# Pendu_LED_Arrow.net
KiCad netlist of a schematic drawn in EasyEDA
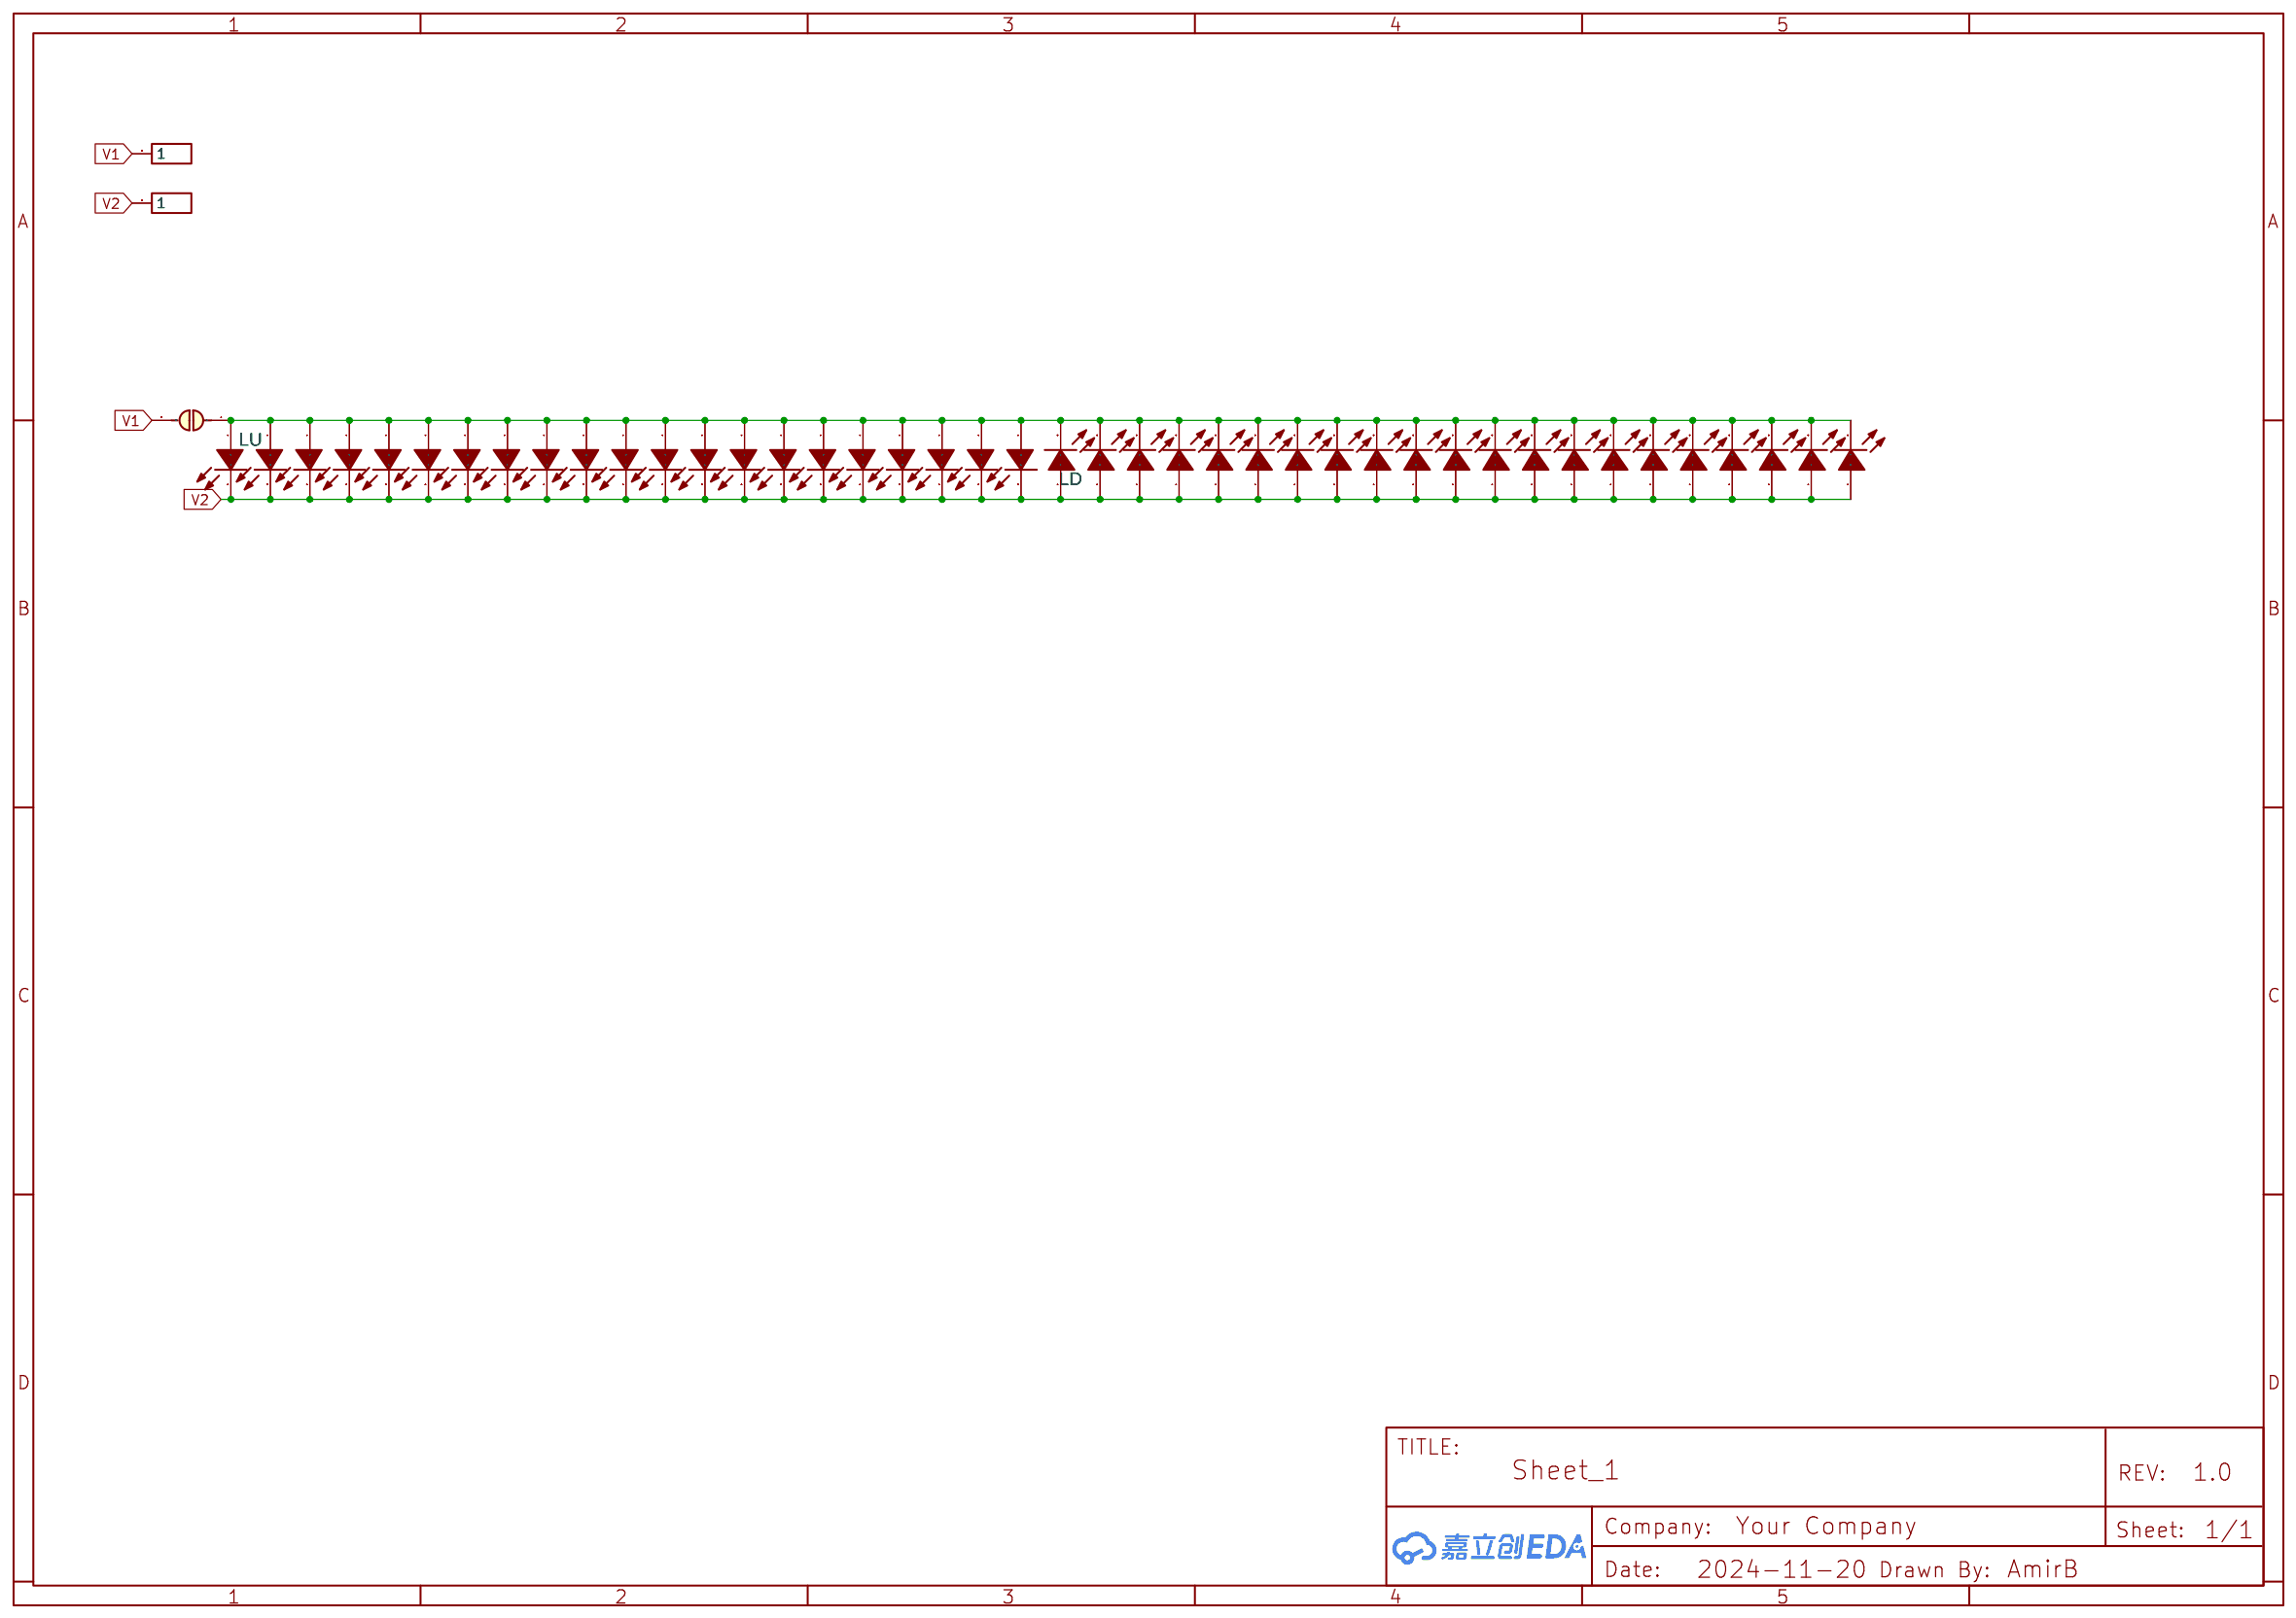
[diagram p0: schematic sheet]

(export (version "E")
  (design (tool "Eeschema 10.0.6"))
  (components
    (comp (ref "J1")
      (value "HDR-M-2.54_1x1")
      (fields (field (name "BOM_Supplier Part") "C81276"))
      (libsource (lib "") (part "HDR-M-2.54_1x1"))
    )
    (comp (ref "J2")
      (value "HDR-M-2.54_1x1")
      (fields (field (name "BOM_Supplier Part") "C81276"))
      (libsource (lib "") (part "HDR-M-2.54_1x1"))
    )
    (comp (ref "JU1") (value "JUMPER-RESET") (libsource (lib "") (part "JUMPER-SMT_2")))
    (comp (ref "LD")
      (value "FC-2012HRK-620D")
      (fields (field (name "Manufacturer Part") "NCD0805R1") (field (name "Manufacturer") "国星光电"))
      (libsource (lib "") (part "FC-2012HRK-620D_1"))
    )
    (comp (ref "LD1")
      (value "FC-2012HRK-620D")
      (fields (field (name "Manufacturer Part") "NCD0805R1") (field (name "Manufacturer") "国星光电"))
      (libsource (lib "") (part "FC-2012HRK-620D_1"))
    )
    (comp (ref "LD2")
      (value "FC-2012HRK-620D")
      (fields (field (name "Manufacturer Part") "NCD0805R1") (field (name "Manufacturer") "国星光电"))
      (libsource (lib "") (part "FC-2012HRK-620D_1"))
    )
    (comp (ref "LD3")
      (value "FC-2012HRK-620D")
      (fields (field (name "Manufacturer Part") "NCD0805R1") (field (name "Manufacturer") "国星光电"))
      (libsource (lib "") (part "FC-2012HRK-620D_1"))
    )
    (comp (ref "LD4")
      (value "FC-2012HRK-620D")
      (fields (field (name "Manufacturer Part") "NCD0805R1") (field (name "Manufacturer") "国星光电"))
      (libsource (lib "") (part "FC-2012HRK-620D_1"))
    )
    (comp (ref "LD5")
      (value "FC-2012HRK-620D")
      (fields (field (name "Manufacturer Part") "NCD0805R1") (field (name "Manufacturer") "国星光电"))
      (libsource (lib "") (part "FC-2012HRK-620D_1"))
    )
    (comp (ref "LD6")
      (value "FC-2012HRK-620D")
      (fields (field (name "Manufacturer Part") "NCD0805R1") (field (name "Manufacturer") "国星光电"))
      (libsource (lib "") (part "FC-2012HRK-620D_1"))
    )
    (comp (ref "LD7")
      (value "FC-2012HRK-620D")
      (fields (field (name "Manufacturer Part") "NCD0805R1") (field (name "Manufacturer") "国星光电"))
      (libsource (lib "") (part "FC-2012HRK-620D_1"))
    )
    (comp (ref "LD8")
      (value "FC-2012HRK-620D")
      (fields (field (name "Manufacturer Part") "NCD0805R1") (field (name "Manufacturer") "国星光电"))
      (libsource (lib "") (part "FC-2012HRK-620D_1"))
    )
    (comp (ref "LD9")
      (value "FC-2012HRK-620D")
      (fields (field (name "Manufacturer Part") "NCD0805R1") (field (name "Manufacturer") "国星光电"))
      (libsource (lib "") (part "FC-2012HRK-620D_1"))
    )
    (comp (ref "LD10")
      (value "FC-2012HRK-620D")
      (fields (field (name "Manufacturer Part") "NCD0805R1") (field (name "Manufacturer") "国星光电"))
      (libsource (lib "") (part "FC-2012HRK-620D_1"))
    )
    (comp (ref "LD11")
      (value "FC-2012HRK-620D")
      (fields (field (name "Manufacturer Part") "NCD0805R1") (field (name "Manufacturer") "国星光电"))
      (libsource (lib "") (part "FC-2012HRK-620D_1"))
    )
    (comp (ref "LD12")
      (value "FC-2012HRK-620D")
      (fields (field (name "Manufacturer Part") "NCD0805R1") (field (name "Manufacturer") "国星光电"))
      (libsource (lib "") (part "FC-2012HRK-620D_1"))
    )
    (comp (ref "LD13")
      (value "FC-2012HRK-620D")
      (fields (field (name "Manufacturer Part") "NCD0805R1") (field (name "Manufacturer") "国星光电"))
      (libsource (lib "") (part "FC-2012HRK-620D_1"))
    )
    (comp (ref "LD14")
      (value "FC-2012HRK-620D")
      (fields (field (name "Manufacturer Part") "NCD0805R1") (field (name "Manufacturer") "国星光电"))
      (libsource (lib "") (part "FC-2012HRK-620D_1"))
    )
    (comp (ref "LD15")
      (value "FC-2012HRK-620D")
      (fields (field (name "Manufacturer Part") "NCD0805R1") (field (name "Manufacturer") "国星光电"))
      (libsource (lib "") (part "FC-2012HRK-620D_1"))
    )
    (comp (ref "LD16")
      (value "FC-2012HRK-620D")
      (fields (field (name "Manufacturer Part") "NCD0805R1") (field (name "Manufacturer") "国星光电"))
      (libsource (lib "") (part "FC-2012HRK-620D_1"))
    )
    (comp (ref "LD17")
      (value "FC-2012HRK-620D")
      (fields (field (name "Manufacturer Part") "NCD0805R1") (field (name "Manufacturer") "国星光电"))
      (libsource (lib "") (part "FC-2012HRK-620D_1"))
    )
    (comp (ref "LD18")
      (value "FC-2012HRK-620D")
      (fields (field (name "Manufacturer Part") "NCD0805R1") (field (name "Manufacturer") "国星光电"))
      (libsource (lib "") (part "FC-2012HRK-620D_1"))
    )
    (comp (ref "LD19")
      (value "FC-2012HRK-620D")
      (fields (field (name "Manufacturer Part") "NCD0805R1") (field (name "Manufacturer") "国星光电"))
      (libsource (lib "") (part "FC-2012HRK-620D_1"))
    )
    (comp (ref "LD20")
      (value "FC-2012HRK-620D")
      (fields (field (name "Manufacturer Part") "NCD0805R1") (field (name "Manufacturer") "国星光电"))
      (libsource (lib "") (part "FC-2012HRK-620D_1"))
    )
    (comp (ref "LU")
      (value "FC-2012HRK-620D")
      (fields (field (name "Manufacturer Part") "NCD0805R1") (field (name "Manufacturer") "国星光电"))
      (libsource (lib "") (part "FC-2012HRK-620D"))
    )
    (comp (ref "LU1")
      (value "FC-2012HRK-620D")
      (fields (field (name "Manufacturer Part") "NCD0805R1") (field (name "Manufacturer") "国星光电"))
      (libsource (lib "") (part "FC-2012HRK-620D"))
    )
    (comp (ref "LU2")
      (value "FC-2012HRK-620D")
      (fields (field (name "Manufacturer Part") "NCD0805R1") (field (name "Manufacturer") "国星光电"))
      (libsource (lib "") (part "FC-2012HRK-620D"))
    )
    (comp (ref "LU3")
      (value "FC-2012HRK-620D")
      (fields (field (name "Manufacturer Part") "NCD0805R1") (field (name "Manufacturer") "国星光电"))
      (libsource (lib "") (part "FC-2012HRK-620D"))
    )
    (comp (ref "LU4")
      (value "FC-2012HRK-620D")
      (fields (field (name "Manufacturer Part") "NCD0805R1") (field (name "Manufacturer") "国星光电"))
      (libsource (lib "") (part "FC-2012HRK-620D"))
    )
    (comp (ref "LU5")
      (value "FC-2012HRK-620D")
      (fields (field (name "Manufacturer Part") "NCD0805R1") (field (name "Manufacturer") "国星光电"))
      (libsource (lib "") (part "FC-2012HRK-620D"))
    )
    (comp (ref "LU6")
      (value "FC-2012HRK-620D")
      (fields (field (name "Manufacturer Part") "NCD0805R1") (field (name "Manufacturer") "国星光电"))
      (libsource (lib "") (part "FC-2012HRK-620D"))
    )
    (comp (ref "LU7")
      (value "FC-2012HRK-620D")
      (fields (field (name "Manufacturer Part") "NCD0805R1") (field (name "Manufacturer") "国星光电"))
      (libsource (lib "") (part "FC-2012HRK-620D"))
    )
    (comp (ref "LU8")
      (value "FC-2012HRK-620D")
      (fields (field (name "Manufacturer Part") "NCD0805R1") (field (name "Manufacturer") "国星光电"))
      (libsource (lib "") (part "FC-2012HRK-620D"))
    )
    (comp (ref "LU9")
      (value "FC-2012HRK-620D")
      (fields (field (name "Manufacturer Part") "NCD0805R1") (field (name "Manufacturer") "国星光电"))
      (libsource (lib "") (part "FC-2012HRK-620D"))
    )
    (comp (ref "LU10")
      (value "FC-2012HRK-620D")
      (fields (field (name "Manufacturer Part") "NCD0805R1") (field (name "Manufacturer") "国星光电"))
      (libsource (lib "") (part "FC-2012HRK-620D"))
    )
    (comp (ref "LU11")
      (value "FC-2012HRK-620D")
      (fields (field (name "Manufacturer Part") "NCD0805R1") (field (name "Manufacturer") "国星光电"))
      (libsource (lib "") (part "FC-2012HRK-620D"))
    )
    (comp (ref "LU12")
      (value "FC-2012HRK-620D")
      (fields (field (name "Manufacturer Part") "NCD0805R1") (field (name "Manufacturer") "国星光电"))
      (libsource (lib "") (part "FC-2012HRK-620D"))
    )
    (comp (ref "LU13")
      (value "FC-2012HRK-620D")
      (fields (field (name "Manufacturer Part") "NCD0805R1") (field (name "Manufacturer") "国星光电"))
      (libsource (lib "") (part "FC-2012HRK-620D"))
    )
    (comp (ref "LU14")
      (value "FC-2012HRK-620D")
      (fields (field (name "Manufacturer Part") "NCD0805R1") (field (name "Manufacturer") "国星光电"))
      (libsource (lib "") (part "FC-2012HRK-620D"))
    )
    (comp (ref "LU15")
      (value "FC-2012HRK-620D")
      (fields (field (name "Manufacturer Part") "NCD0805R1") (field (name "Manufacturer") "国星光电"))
      (libsource (lib "") (part "FC-2012HRK-620D"))
    )
    (comp (ref "LU16")
      (value "FC-2012HRK-620D")
      (fields (field (name "Manufacturer Part") "NCD0805R1") (field (name "Manufacturer") "国星光电"))
      (libsource (lib "") (part "FC-2012HRK-620D"))
    )
    (comp (ref "LU17")
      (value "FC-2012HRK-620D")
      (fields (field (name "Manufacturer Part") "NCD0805R1") (field (name "Manufacturer") "国星光电"))
      (libsource (lib "") (part "FC-2012HRK-620D"))
    )
    (comp (ref "LU18")
      (value "FC-2012HRK-620D")
      (fields (field (name "Manufacturer Part") "NCD0805R1") (field (name "Manufacturer") "国星光电"))
      (libsource (lib "") (part "FC-2012HRK-620D"))
    )
    (comp (ref "LU19")
      (value "FC-2012HRK-620D")
      (fields (field (name "Manufacturer Part") "NCD0805R1") (field (name "Manufacturer") "国星光电"))
      (libsource (lib "") (part "FC-2012HRK-620D"))
    )
    (comp (ref "LU20")
      (value "FC-2012HRK-620D")
      (fields (field (name "Manufacturer Part") "NCD0805R1") (field (name "Manufacturer") "国星光电"))
      (libsource (lib "") (part "FC-2012HRK-620D"))
    )
  )
  (nets
    (net (code "1") (name "Net-(LD--)") (class "Default")
      (node (ref "JU1") (pin "1") (pinfunction "1_1") (pintype "bidirectional"))
      (node (ref "LD") (pin "2") (pinfunction "-_2") (pintype "unspecified"))
      (node (ref "LD1") (pin "2") (pinfunction "-_2") (pintype "unspecified"))
      (node (ref "LD10") (pin "2") (pinfunction "-_2") (pintype "unspecified"))
      (node (ref "LD11") (pin "2") (pinfunction "-_2") (pintype "unspecified"))
      (node (ref "LD12") (pin "2") (pinfunction "-_2") (pintype "unspecified"))
      (node (ref "LD13") (pin "2") (pinfunction "-_2") (pintype "unspecified"))
      (node (ref "LD14") (pin "2") (pinfunction "-_2") (pintype "unspecified"))
      (node (ref "LD15") (pin "2") (pinfunction "-_2") (pintype "unspecified"))
      (node (ref "LD16") (pin "2") (pinfunction "-_2") (pintype "unspecified"))
      (node (ref "LD17") (pin "2") (pinfunction "-_2") (pintype "unspecified"))
      (node (ref "LD18") (pin "2") (pinfunction "-_2") (pintype "unspecified"))
      (node (ref "LD19") (pin "2") (pinfunction "-_2") (pintype "unspecified"))
      (node (ref "LD2") (pin "2") (pinfunction "-_2") (pintype "unspecified"))
      (node (ref "LD20") (pin "2") (pinfunction "-_2") (pintype "unspecified"))
      (node (ref "LD3") (pin "2") (pinfunction "-_2") (pintype "unspecified"))
      (node (ref "LD4") (pin "2") (pinfunction "-_2") (pintype "unspecified"))
      (node (ref "LD5") (pin "2") (pinfunction "-_2") (pintype "unspecified"))
      (node (ref "LD6") (pin "2") (pinfunction "-_2") (pintype "unspecified"))
      (node (ref "LD7") (pin "2") (pinfunction "-_2") (pintype "unspecified"))
      (node (ref "LD8") (pin "2") (pinfunction "-_2") (pintype "unspecified"))
      (node (ref "LD9") (pin "2") (pinfunction "-_2") (pintype "unspecified"))
      (node (ref "LU") (pin "1") (pinfunction "+_1") (pintype "unspecified"))
      (node (ref "LU1") (pin "1") (pinfunction "+_1") (pintype "unspecified"))
      (node (ref "LU10") (pin "1") (pinfunction "+_1") (pintype "unspecified"))
      (node (ref "LU11") (pin "1") (pinfunction "+_1") (pintype "unspecified"))
      (node (ref "LU12") (pin "1") (pinfunction "+_1") (pintype "unspecified"))
      (node (ref "LU13") (pin "1") (pinfunction "+_1") (pintype "unspecified"))
      (node (ref "LU14") (pin "1") (pinfunction "+_1") (pintype "unspecified"))
      (node (ref "LU15") (pin "1") (pinfunction "+_1") (pintype "unspecified"))
      (node (ref "LU16") (pin "1") (pinfunction "+_1") (pintype "unspecified"))
      (node (ref "LU17") (pin "1") (pinfunction "+_1") (pintype "unspecified"))
      (node (ref "LU18") (pin "1") (pinfunction "+_1") (pintype "unspecified"))
      (node (ref "LU19") (pin "1") (pinfunction "+_1") (pintype "unspecified"))
      (node (ref "LU2") (pin "1") (pinfunction "+_1") (pintype "unspecified"))
      (node (ref "LU20") (pin "1") (pinfunction "+_1") (pintype "unspecified"))
      (node (ref "LU3") (pin "1") (pinfunction "+_1") (pintype "unspecified"))
      (node (ref "LU4") (pin "1") (pinfunction "+_1") (pintype "unspecified"))
      (node (ref "LU5") (pin "1") (pinfunction "+_1") (pintype "unspecified"))
      (node (ref "LU6") (pin "1") (pinfunction "+_1") (pintype "unspecified"))
      (node (ref "LU7") (pin "1") (pinfunction "+_1") (pintype "unspecified"))
      (node (ref "LU8") (pin "1") (pinfunction "+_1") (pintype "unspecified"))
      (node (ref "LU9") (pin "1") (pinfunction "+_1") (pintype "unspecified"))
    )
    (net (code "2") (name "V1") (class "Default")
      (node (ref "J1") (pin "1") (pinfunction "1_1") (pintype "input"))
      (node (ref "JU1") (pin "2") (pinfunction "2_2") (pintype "bidirectional"))
    )
    (net (code "3") (name "V2") (class "Default")
      (node (ref "J2") (pin "1") (pinfunction "1_1") (pintype "input"))
      (node (ref "LD") (pin "1") (pinfunction "+_1") (pintype "unspecified"))
      (node (ref "LD1") (pin "1") (pinfunction "+_1") (pintype "unspecified"))
      (node (ref "LD10") (pin "1") (pinfunction "+_1") (pintype "unspecified"))
      (node (ref "LD11") (pin "1") (pinfunction "+_1") (pintype "unspecified"))
      (node (ref "LD12") (pin "1") (pinfunction "+_1") (pintype "unspecified"))
      (node (ref "LD13") (pin "1") (pinfunction "+_1") (pintype "unspecified"))
      (node (ref "LD14") (pin "1") (pinfunction "+_1") (pintype "unspecified"))
      (node (ref "LD15") (pin "1") (pinfunction "+_1") (pintype "unspecified"))
      (node (ref "LD16") (pin "1") (pinfunction "+_1") (pintype "unspecified"))
      (node (ref "LD17") (pin "1") (pinfunction "+_1") (pintype "unspecified"))
      (node (ref "LD18") (pin "1") (pinfunction "+_1") (pintype "unspecified"))
      (node (ref "LD19") (pin "1") (pinfunction "+_1") (pintype "unspecified"))
      (node (ref "LD2") (pin "1") (pinfunction "+_1") (pintype "unspecified"))
      (node (ref "LD20") (pin "1") (pinfunction "+_1") (pintype "unspecified"))
      (node (ref "LD3") (pin "1") (pinfunction "+_1") (pintype "unspecified"))
      (node (ref "LD4") (pin "1") (pinfunction "+_1") (pintype "unspecified"))
      (node (ref "LD5") (pin "1") (pinfunction "+_1") (pintype "unspecified"))
      (node (ref "LD6") (pin "1") (pinfunction "+_1") (pintype "unspecified"))
      (node (ref "LD7") (pin "1") (pinfunction "+_1") (pintype "unspecified"))
      (node (ref "LD8") (pin "1") (pinfunction "+_1") (pintype "unspecified"))
      (node (ref "LD9") (pin "1") (pinfunction "+_1") (pintype "unspecified"))
      (node (ref "LU") (pin "2") (pinfunction "-_2") (pintype "unspecified"))
      (node (ref "LU1") (pin "2") (pinfunction "-_2") (pintype "unspecified"))
      (node (ref "LU10") (pin "2") (pinfunction "-_2") (pintype "unspecified"))
      (node (ref "LU11") (pin "2") (pinfunction "-_2") (pintype "unspecified"))
      (node (ref "LU12") (pin "2") (pinfunction "-_2") (pintype "unspecified"))
      (node (ref "LU13") (pin "2") (pinfunction "-_2") (pintype "unspecified"))
      (node (ref "LU14") (pin "2") (pinfunction "-_2") (pintype "unspecified"))
      (node (ref "LU15") (pin "2") (pinfunction "-_2") (pintype "unspecified"))
      (node (ref "LU16") (pin "2") (pinfunction "-_2") (pintype "unspecified"))
      (node (ref "LU17") (pin "2") (pinfunction "-_2") (pintype "unspecified"))
      (node (ref "LU18") (pin "2") (pinfunction "-_2") (pintype "unspecified"))
      (node (ref "LU19") (pin "2") (pinfunction "-_2") (pintype "unspecified"))
      (node (ref "LU2") (pin "2") (pinfunction "-_2") (pintype "unspecified"))
      (node (ref "LU20") (pin "2") (pinfunction "-_2") (pintype "unspecified"))
      (node (ref "LU3") (pin "2") (pinfunction "-_2") (pintype "unspecified"))
      (node (ref "LU4") (pin "2") (pinfunction "-_2") (pintype "unspecified"))
      (node (ref "LU5") (pin "2") (pinfunction "-_2") (pintype "unspecified"))
      (node (ref "LU6") (pin "2") (pinfunction "-_2") (pintype "unspecified"))
      (node (ref "LU7") (pin "2") (pinfunction "-_2") (pintype "unspecified"))
      (node (ref "LU8") (pin "2") (pinfunction "-_2") (pintype "unspecified"))
      (node (ref "LU9") (pin "2") (pinfunction "-_2") (pintype "unspecified"))
    )
  )
)
